# 17.net
KiCad netlist of a schematic drawn in Altium Designer
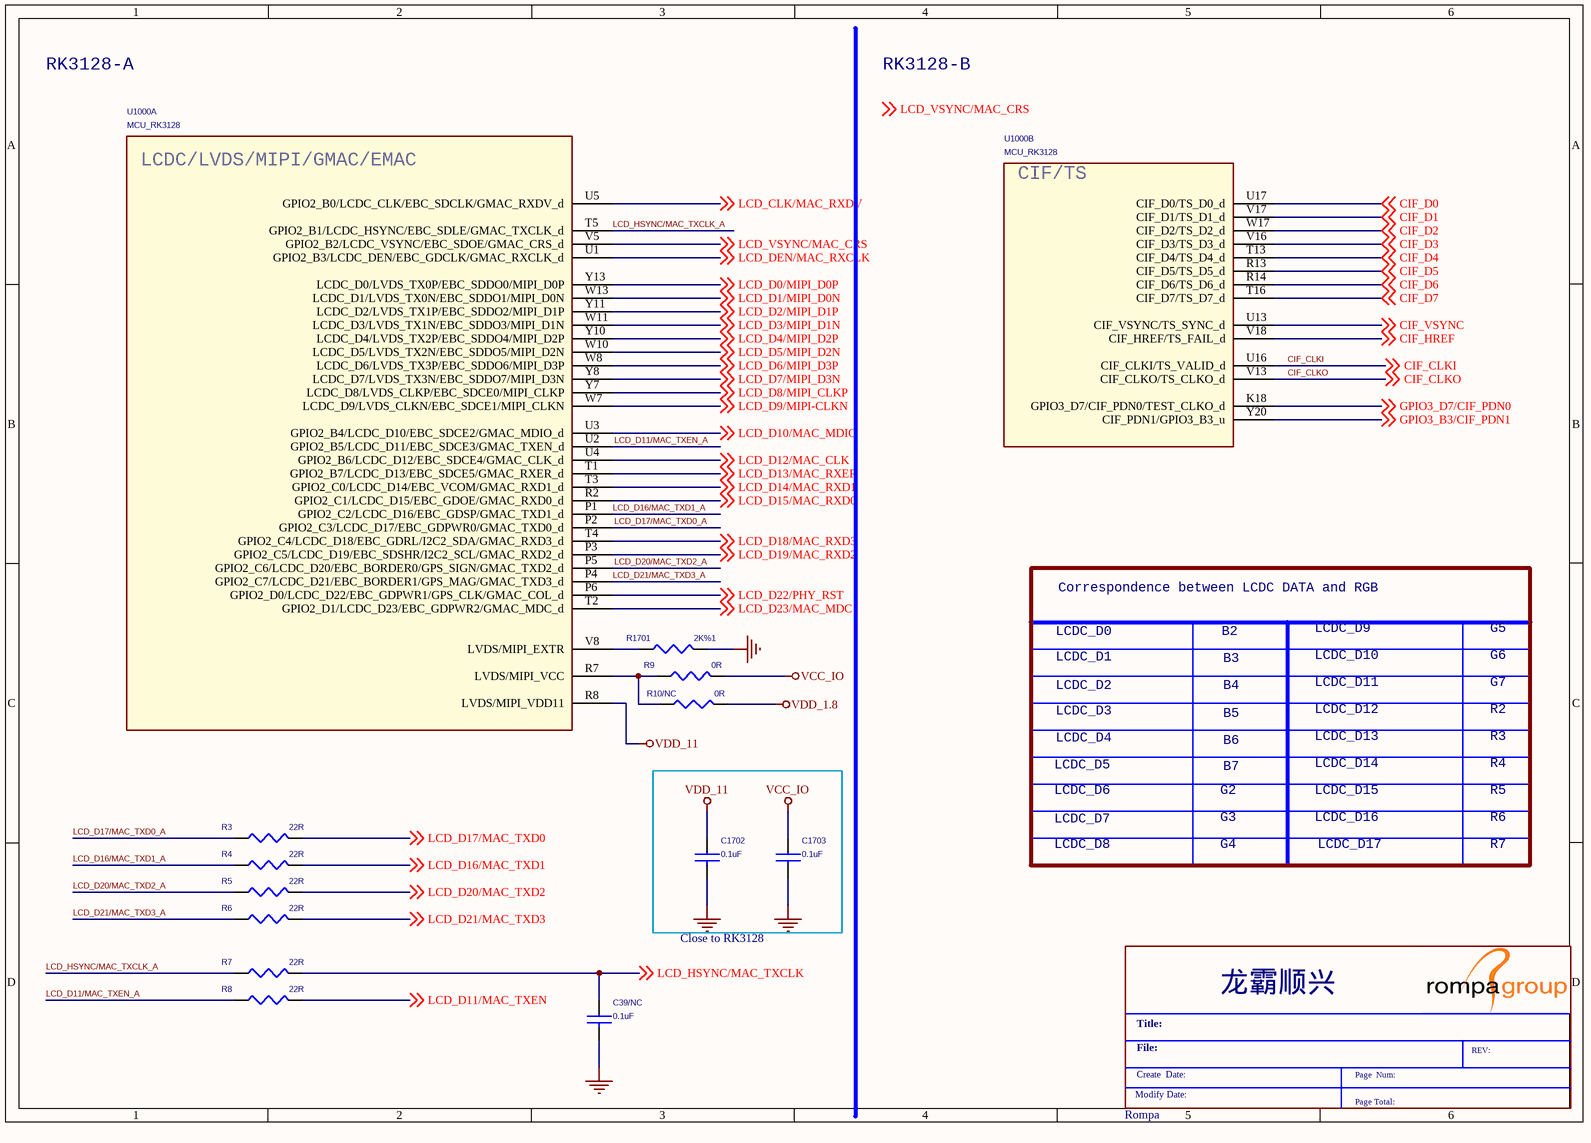
[diagram p0: 17.SchDoc]

(export (version "E")
  (design (tool "Eeschema 10.0.6"))
  (components
    (comp (ref "*") (value "Rompa") (libsource (lib "RK3128_BETA_V03_20151231_Library") (part "Rompa")))
    (comp (ref "C39/NC")
      (value "0.1uF")
      (footprint "C0402")
      (description "RoHS CHIP CAP 0.1uF +10/-10% X7R")
      (libsource (lib "*") (part "CAP NP"))
    )
    (comp (ref "C1702")
      (value "0.1uF")
      (footprint "C0402")
      (description "RoHS CHIP CAP 0.1uF +10/-10% X7R")
      (libsource (lib "*") (part "CAP NP"))
    )
    (comp (ref "C1703")
      (value "0.1uF")
      (footprint "C0402")
      (description "RoHS CHIP CAP 0.1uF +10/-10% X7R")
      (libsource (lib "*") (part "CAP NP"))
    )
    (comp (ref "R3")
      (value "22R")
      (footprint "R0402")
      (description "ROHS CHIP RES 4.7K 1/16W 5%")
      (libsource (lib "*") (part "RES 1B"))
    )
    (comp (ref "R4")
      (value "22R")
      (footprint "R0402")
      (description "ROHS CHIP RES 4.7K 1/16W 5%")
      (libsource (lib "*") (part "RES 1B"))
    )
    (comp (ref "R5")
      (value "22R")
      (footprint "R0402")
      (description "ROHS CHIP RES 4.7K 1/16W 5%")
      (libsource (lib "*") (part "RES 1B"))
    )
    (comp (ref "R6")
      (value "22R")
      (footprint "R0402")
      (description "ROHS CHIP RES 4.7K 1/16W 5%")
      (libsource (lib "*") (part "RES 1B"))
    )
    (comp (ref "R7")
      (value "22R")
      (footprint "R0402")
      (description "ROHS CHIP RES 4.7K 1/16W 5%")
      (libsource (lib "*") (part "RES 1B"))
    )
    (comp (ref "R8")
      (value "22R")
      (footprint "R0402")
      (description "ROHS CHIP RES 4.7K 1/16W 5%")
      (libsource (lib "*") (part "RES 1B"))
    )
    (comp (ref "R9")
      (value "0R")
      (footprint "R0402")
      (description "ROHS CHIP RES 4.7K 1/16W 5%")
      (libsource (lib "*") (part "RES 1B"))
    )
    (comp (ref "R10/NC")
      (value "0R")
      (footprint "R0402")
      (description "NC/ 0R")
      (libsource (lib "*") (part "RES 1B"))
    )
    (comp (ref "R1701")
      (value "2K%1")
      (footprint "R0402")
      (description "ROHS CHIP RES 4.7K 1/16W 5%")
      (libsource (lib "*") (part "RES 1B"))
    )
    (comp (ref "U1000")
      (value "MCU_RK3128")
      (footprint "BGA316-14X14-0.65")
      (libsource (lib "*") (part "MCU_RK3128"))
    )
  )
  (nets
    (net (code "1") (name "/LCD_D11{slash}MAC_TXEN_A") (class "Default")
      (node (ref "R8") (pin "1") (pinfunction "1_1") (pintype "passive"))
      (node (ref "U1000") (pin "U2") (pinfunction "GPIO2_B5/LCDC_D11/EBC_SDCE3/GMAC_TXEN_d_U2") (pintype "passive"))
    )
    (net (code "2") (name "/LCD_D16{slash}MAC_TXD1_A") (class "Default")
      (node (ref "R4") (pin "1") (pinfunction "1_1") (pintype "passive"))
      (node (ref "U1000") (pin "P1") (pinfunction "GPIO2_C2/LCDC_D16/EBC_GDSP/GMAC_TXD1_d_P1") (pintype "passive"))
    )
    (net (code "3") (name "/LCD_D17{slash}MAC_TXD0_A") (class "Default")
      (node (ref "R3") (pin "1") (pinfunction "1_1") (pintype "passive"))
      (node (ref "U1000") (pin "P2") (pinfunction "GPIO2_C3/LCDC_D17/EBC_GDPWR0/GMAC_TXD0_d_P2") (pintype "passive"))
    )
    (net (code "4") (name "/LCD_D20{slash}MAC_TXD2_A") (class "Default")
      (node (ref "R5") (pin "1") (pinfunction "1_1") (pintype "passive"))
      (node (ref "U1000") (pin "P5") (pinfunction "GPIO2_C6/LCDC_D20/EBC_BORDER0/GPS_SIGN/GMAC_TXD2_d_P5") (pintype "passive"))
    )
    (net (code "5") (name "/LCD_D21{slash}MAC_TXD3_A") (class "Default")
      (node (ref "R6") (pin "1") (pinfunction "1_1") (pintype "passive"))
      (node (ref "U1000") (pin "P4") (pinfunction "GPIO2_C7/LCDC_D21/EBC_BORDER1/GPS_MAG/GMAC_TXD3_d_P4") (pintype "passive"))
    )
    (net (code "6") (name "/LCD_HSYNC{slash}MAC_TXCLK_A") (class "Default")
      (node (ref "R7") (pin "1") (pinfunction "1_1") (pintype "passive"))
      (node (ref "U1000") (pin "T5") (pinfunction "GPIO2_B1/LCDC_HSYNC/EBC_SDLE/GMAC_TXCLK_d_T5") (pintype "passive"))
    )
    (net (code "7") (name "CIF_CLKI") (class "Default")
      (node (ref "U1000") (pin "U16") (pinfunction "CIF_CLKI/TS_VALID_d_U16") (pintype "passive"))
    )
    (net (code "8") (name "CIF_CLKO") (class "Default")
      (node (ref "U1000") (pin "V13") (pinfunction "CIF_CLKO/TS_CLKO_d_V13") (pintype "passive"))
    )
    (net (code "9") (name "CIF_D0") (class "Default")
      (node (ref "U1000") (pin "U17") (pinfunction "CIF_D0/TS_D0_d_U17") (pintype "passive"))
    )
    (net (code "10") (name "CIF_D1") (class "Default")
      (node (ref "U1000") (pin "V17") (pinfunction "CIF_D1/TS_D1_d_V17") (pintype "passive"))
    )
    (net (code "11") (name "CIF_D2") (class "Default")
      (node (ref "U1000") (pin "W17") (pinfunction "CIF_D2/TS_D2_d_W17") (pintype "passive"))
    )
    (net (code "12") (name "CIF_D3") (class "Default")
      (node (ref "U1000") (pin "V16") (pinfunction "CIF_D3/TS_D3_d_V16") (pintype "passive"))
    )
    (net (code "13") (name "CIF_D4") (class "Default")
      (node (ref "U1000") (pin "T13") (pinfunction "CIF_D4/TS_D4_d_T13") (pintype "passive"))
    )
    (net (code "14") (name "CIF_D5") (class "Default")
      (node (ref "U1000") (pin "R13") (pinfunction "CIF_D5/TS_D5_d_R13") (pintype "passive"))
    )
    (net (code "15") (name "CIF_D6") (class "Default")
      (node (ref "U1000") (pin "R14") (pinfunction "CIF_D6/TS_D6_d_R14") (pintype "passive"))
    )
    (net (code "16") (name "CIF_D7") (class "Default")
      (node (ref "U1000") (pin "T16") (pinfunction "CIF_D7/TS_D7_d_T16") (pintype "passive"))
    )
    (net (code "17") (name "CIF_HREF") (class "Default")
      (node (ref "U1000") (pin "V18") (pinfunction "CIF_HREF/TS_FAIL_d_V18") (pintype "passive"))
    )
    (net (code "18") (name "CIF_VSYNC") (class "Default")
      (node (ref "U1000") (pin "U13") (pinfunction "CIF_VSYNC/TS_SYNC_d_U13") (pintype "passive"))
    )
    (net (code "19") (name "GND") (class "Default")
      (node (ref "C1702") (pin "2") (pinfunction "2_2") (pintype "passive"))
      (node (ref "C1703") (pin "2") (pinfunction "2_2") (pintype "passive"))
      (node (ref "C39/NC") (pin "2") (pinfunction "2_2") (pintype "passive"))
      (node (ref "R1701") (pin "2") (pinfunction "2_2") (pintype "passive"))
    )
    (net (code "20") (name "GPIO3_B3{slash}CIF_PDN1") (class "Default")
      (node (ref "U1000") (pin "Y20") (pinfunction "CIF_PDN1/GPIO3_B3_u_Y20") (pintype "passive"))
    )
    (net (code "21") (name "GPIO3_D7{slash}CIF_PDN0") (class "Default")
      (node (ref "U1000") (pin "K18") (pinfunction "GPIO3_D7/CIF_PDN0/TEST_CLKO_d_K18") (pintype "passive"))
    )
    (net (code "22") (name "LCD_CLK{slash}MAC_RXDV") (class "Default")
      (node (ref "U1000") (pin "U5") (pinfunction "GPIO2_B0/LCDC_CLK/EBC_SDCLK/GMAC_RXDV_d_U5") (pintype "passive"))
    )
    (net (code "23") (name "LCD_D0{slash}MIPI_D0P") (class "Default")
      (node (ref "U1000") (pin "Y13") (pinfunction "LCDC_D0/LVDS_TX0P/EBC_SDDO0/MIPI_D0P_Y13") (pintype "passive"))
    )
    (net (code "24") (name "LCD_D1{slash}MIPI_D0N") (class "Default")
      (node (ref "U1000") (pin "W13") (pinfunction "LCDC_D1/LVDS_TX0N/EBC_SDDO1/MIPI_D0N_W13") (pintype "passive"))
    )
    (net (code "25") (name "LCD_D2{slash}MIPI_D1P") (class "Default")
      (node (ref "U1000") (pin "Y11") (pinfunction "LCDC_D2/LVDS_TX1P/EBC_SDDO2/MIPI_D1P_Y11") (pintype "passive"))
    )
    (net (code "26") (name "LCD_D3{slash}MIPI_D1N") (class "Default")
      (node (ref "U1000") (pin "W11") (pinfunction "LCDC_D3/LVDS_TX1N/EBC_SDDO3/MIPI_D1N_W11") (pintype "passive"))
    )
    (net (code "27") (name "LCD_D4{slash}MIPI_D2P") (class "Default")
      (node (ref "U1000") (pin "Y10") (pinfunction "LCDC_D4/LVDS_TX2P/EBC_SDDO4/MIPI_D2P_Y10") (pintype "passive"))
    )
    (net (code "28") (name "LCD_D5{slash}MIPI_D2N") (class "Default")
      (node (ref "U1000") (pin "W10") (pinfunction "LCDC_D5/LVDS_TX2N/EBC_SDDO5/MIPI_D2N_W10") (pintype "passive"))
    )
    (net (code "29") (name "LCD_D6{slash}MIPI_D3P") (class "Default")
      (node (ref "U1000") (pin "W8") (pinfunction "LCDC_D6/LVDS_TX3P/EBC_SDDO6/MIPI_D3P_W8") (pintype "passive"))
    )
    (net (code "30") (name "LCD_D7{slash}MIPI_D3N") (class "Default")
      (node (ref "U1000") (pin "Y8") (pinfunction "LCDC_D7/LVDS_TX3N/EBC_SDDO7/MIPI_D3N_Y8") (pintype "passive"))
    )
    (net (code "31") (name "LCD_D8{slash}MIPI_CLKP") (class "Default")
      (node (ref "U1000") (pin "Y7") (pinfunction "LCDC_D8/LVDS_CLKP/EBC_SDCE0/MIPI_CLKP_Y7") (pintype "passive"))
    )
    (net (code "32") (name "LCD_D9{slash}MIPI-CLKN") (class "Default")
      (node (ref "U1000") (pin "W7") (pinfunction "LCDC_D9/LVDS_CLKN/EBC_SDCE1/MIPI_CLKN_W7") (pintype "passive"))
    )
    (net (code "33") (name "LCD_D10{slash}MAC_MDIO") (class "Default")
      (node (ref "U1000") (pin "U3") (pinfunction "GPIO2_B4/LCDC_D10/EBC_SDCE2/GMAC_MDIO_d_U3") (pintype "passive"))
    )
    (net (code "34") (name "LCD_D11{slash}MAC_TXEN") (class "Default")
      (node (ref "R8") (pin "2") (pinfunction "2_2") (pintype "passive"))
    )
    (net (code "35") (name "LCD_D12{slash}MAC_CLK") (class "Default")
      (node (ref "U1000") (pin "U4") (pinfunction "GPIO2_B6/LCDC_D12/EBC_SDCE4/GMAC_CLK_d_U4") (pintype "passive"))
    )
    (net (code "36") (name "LCD_D13{slash}MAC_RXER") (class "Default")
      (node (ref "U1000") (pin "T1") (pinfunction "GPIO2_B7/LCDC_D13/EBC_SDCE5/GMAC_RXER_d_T1") (pintype "passive"))
    )
    (net (code "37") (name "LCD_D14{slash}MAC_RXD1") (class "Default")
      (node (ref "U1000") (pin "T3") (pinfunction "GPIO2_C0/LCDC_D14/EBC_VCOM/GMAC_RXD1_d_T3") (pintype "passive"))
    )
    (net (code "38") (name "LCD_D15{slash}MAC_RXD0") (class "Default")
      (node (ref "U1000") (pin "R2") (pinfunction "GPIO2_C1/LCDC_D15/EBC_GDOE/GMAC_RXD0_d_R2") (pintype "passive"))
    )
    (net (code "39") (name "LCD_D16{slash}MAC_TXD1") (class "Default")
      (node (ref "R4") (pin "2") (pinfunction "2_2") (pintype "passive"))
    )
    (net (code "40") (name "LCD_D17{slash}MAC_TXD0") (class "Default")
      (node (ref "R3") (pin "2") (pinfunction "2_2") (pintype "passive"))
    )
    (net (code "41") (name "LCD_D18{slash}MAC_RXD3") (class "Default")
      (node (ref "U1000") (pin "T4") (pinfunction "GPIO2_C4/LCDC_D18/EBC_GDRL/I2C2_SDA/GMAC_RXD3_d_T4") (pintype "passive"))
    )
    (net (code "42") (name "LCD_D19{slash}MAC_RXD2") (class "Default")
      (node (ref "U1000") (pin "P3") (pinfunction "GPIO2_C5/LCDC_D19/EBC_SDSHR/I2C2_SCL/GMAC_RXD2_d_P3") (pintype "passive"))
    )
    (net (code "43") (name "LCD_D20{slash}MAC_TXD2") (class "Default")
      (node (ref "R5") (pin "2") (pinfunction "2_2") (pintype "passive"))
    )
    (net (code "44") (name "LCD_D21{slash}MAC_TXD3") (class "Default")
      (node (ref "R6") (pin "2") (pinfunction "2_2") (pintype "passive"))
    )
    (net (code "45") (name "LCD_D22{slash}PHY_RST") (class "Default")
      (node (ref "U1000") (pin "P6") (pinfunction "GPIO2_D0/LCDC_D22/EBC_GDPWR1/GPS_CLK/GMAC_COL_d_P6") (pintype "passive"))
    )
    (net (code "46") (name "LCD_D23{slash}MAC_MDC") (class "Default")
      (node (ref "U1000") (pin "T2") (pinfunction "GPIO2_D1/LCDC_D23/EBC_GDPWR2/GMAC_MDC_d_T2") (pintype "passive"))
    )
    (net (code "47") (name "LCD_DEN{slash}MAC_RXCLK") (class "Default")
      (node (ref "U1000") (pin "U1") (pinfunction "GPIO2_B3/LCDC_DEN/EBC_GDCLK/GMAC_RXCLK_d_U1") (pintype "passive"))
    )
    (net (code "48") (name "LCD_HSYNC{slash}MAC_TXCLK") (class "Default")
      (node (ref "C39/NC") (pin "1") (pinfunction "1_1") (pintype "passive"))
      (node (ref "R7") (pin "2") (pinfunction "2_2") (pintype "passive"))
    )
    (net (code "49") (name "LCD_VSYNC{slash}MAC_CRS") (class "Default")
      (node (ref "U1000") (pin "V5") (pinfunction "GPIO2_B2/LCDC_VSYNC/EBC_SDOE/GMAC_CRS_d_V5") (pintype "passive"))
    )
    (net (code "50") (name "Net-(U1000A-LVDS{slash}MIPI_EXTR)") (class "Default")
      (node (ref "R1701") (pin "1") (pinfunction "1_1") (pintype "passive"))
      (node (ref "U1000") (pin "V8") (pinfunction "LVDS/MIPI_EXTR_V8") (pintype "passive"))
    )
    (net (code "51") (name "Net-(U1000A-LVDS{slash}MIPI_VCC)") (class "Default")
      (node (ref "R10/NC") (pin "1") (pinfunction "1_1") (pintype "passive"))
      (node (ref "R9") (pin "1") (pinfunction "1_1") (pintype "passive"))
      (node (ref "U1000") (pin "R7") (pinfunction "LVDS/MIPI_VCC_R7") (pintype "passive"))
    )
    (net (code "52") (name "VCC_IO") (class "Default")
      (node (ref "C1703") (pin "1") (pinfunction "1_1") (pintype "passive"))
      (node (ref "R9") (pin "2") (pinfunction "2_2") (pintype "passive"))
    )
    (net (code "53") (name "VDD_1.8") (class "Default")
      (node (ref "R10/NC") (pin "2") (pinfunction "2_2") (pintype "passive"))
    )
    (net (code "54") (name "VDD_11") (class "Default")
      (node (ref "C1702") (pin "1") (pinfunction "1_1") (pintype "passive"))
      (node (ref "U1000") (pin "R8") (pinfunction "LVDS/MIPI_VDD11_R8") (pintype "passive"))
    )
  )
)
